# Group_Project_PCB_first_draft.net
KiCad netlist of a schematic drawn in EAGLE
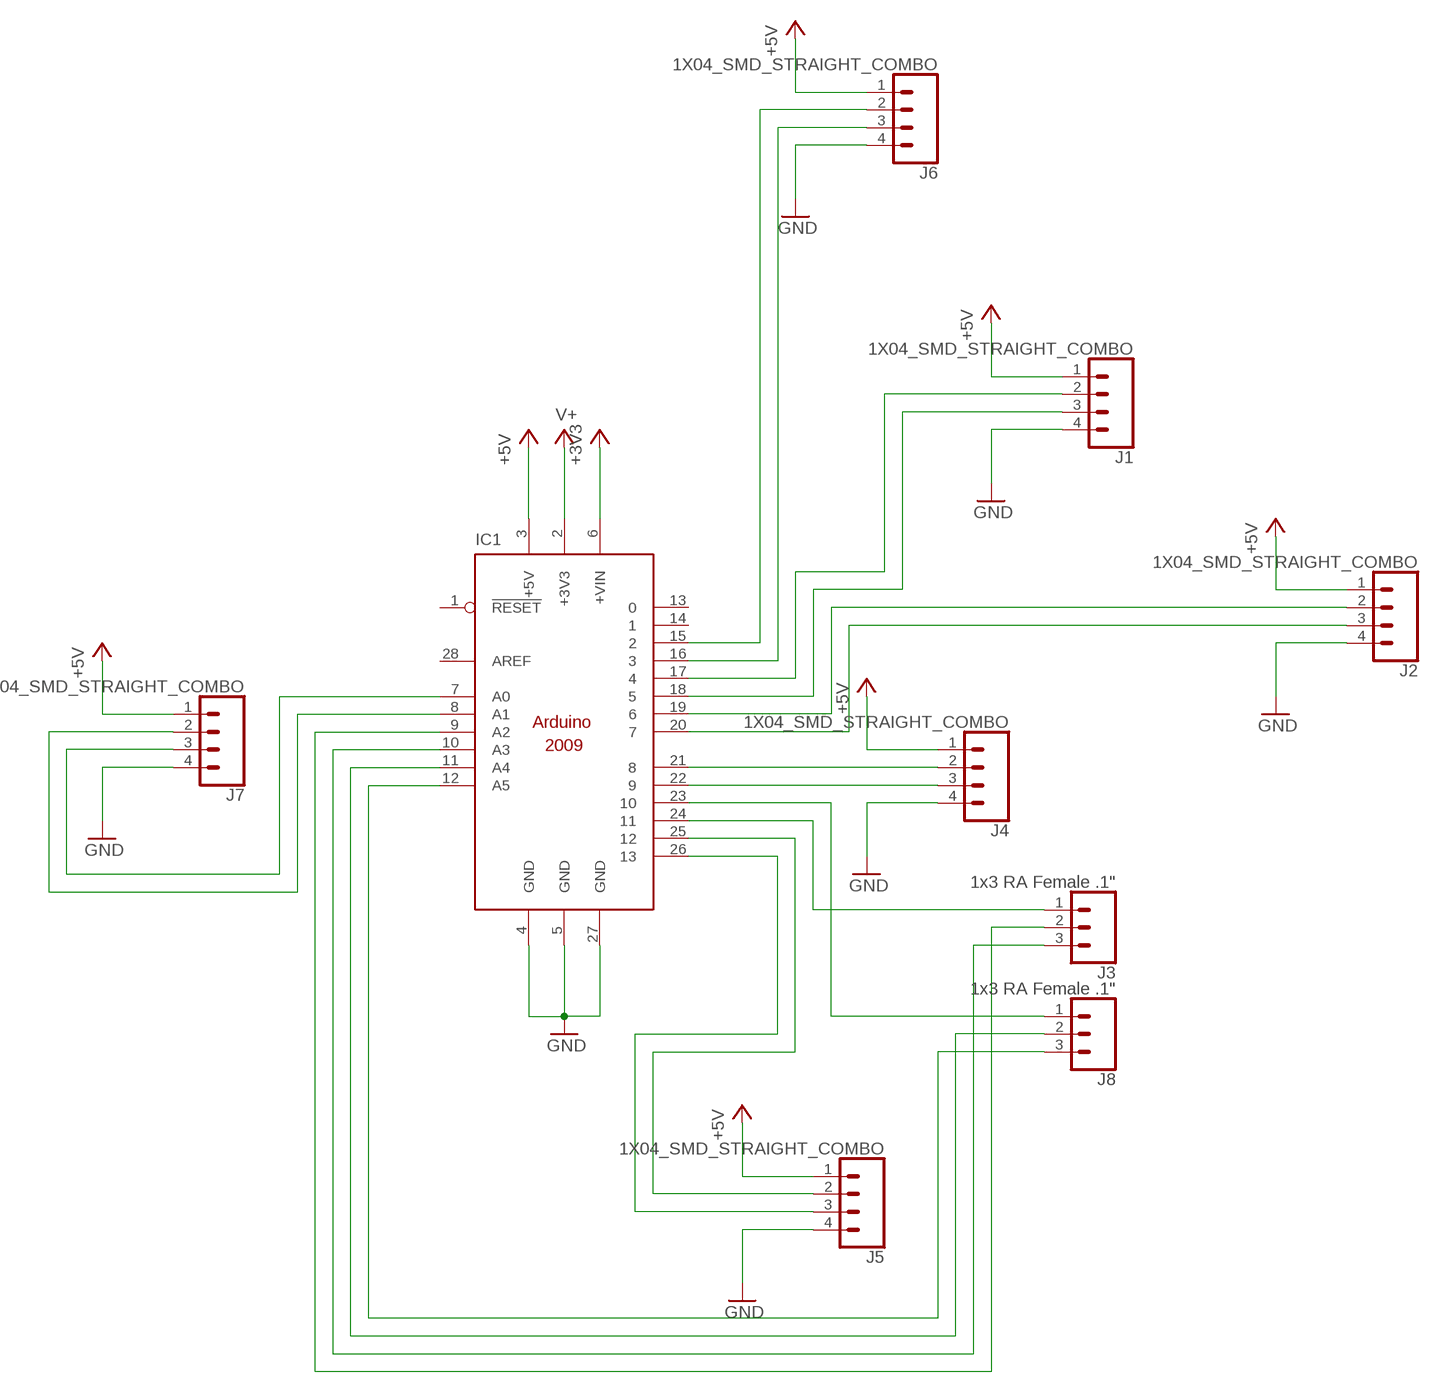
[diagram p0: schematic, sheet 1]

(export (version "E")
  (design (tool "Eeschema 10.0.6"))
  (components
    (comp (ref "IC1")
      (value "ARDUINO2009_10")
      (footprint "eagle-import:ARDUINO2009")
      (libsource (lib "eagle-import") (part "ARDUINO2009_10"))
    )
    (comp (ref "J1")
      (value "1X04_SMD_STRAIGHT_COMBO")
      (footprint "eagle-import:1X04_LONGPADS")
      (libsource (lib "eagle-import") (part "CONN_04LONGPADS"))
    )
    (comp (ref "J2")
      (value "1X04_SMD_STRAIGHT_COMBO")
      (footprint "eagle-import:1X04_LONGPADS")
      (libsource (lib "eagle-import") (part "CONN_04LONGPADS"))
    )
    (comp (ref "J3")
      (value "1x3 RA Female .1\"")
      (footprint "eagle-import:1X03_LONGPADS")
      (libsource (lib "eagle-import") (part "CONN_03LONGPADS"))
    )
    (comp (ref "J4")
      (value "1X04_SMD_STRAIGHT_COMBO")
      (footprint "eagle-import:1X04_LONGPADS")
      (libsource (lib "eagle-import") (part "CONN_04LONGPADS"))
    )
    (comp (ref "J5")
      (value "1X04_SMD_STRAIGHT_COMBO")
      (footprint "eagle-import:1X04_LONGPADS")
      (libsource (lib "eagle-import") (part "CONN_04LONGPADS"))
    )
    (comp (ref "J6")
      (value "1X04_SMD_STRAIGHT_COMBO")
      (footprint "eagle-import:1X04_LONGPADS")
      (libsource (lib "eagle-import") (part "CONN_04LONGPADS"))
    )
    (comp (ref "J7")
      (value "1X04_SMD_STRAIGHT_COMBO")
      (footprint "eagle-import:1X04_LONGPADS")
      (libsource (lib "eagle-import") (part "CONN_04LONGPADS"))
    )
    (comp (ref "J8")
      (value "1x3 RA Female .1\"")
      (footprint "eagle-import:1X03_LONGPADS")
      (libsource (lib "eagle-import") (part "CONN_03LONGPADS"))
    )
  )
  (nets
    (net (code "1") (name "+3V3") (class "Default")
      (node (ref "IC1") (pin "6") (pinfunction "+VIN_6") (pintype "bidirectional"))
    )
    (net (code "2") (name "+5V") (class "Default")
      (node (ref "IC1") (pin "3") (pinfunction "+5V_3") (pintype "power_in"))
      (node (ref "J1") (pin "1") (pinfunction "1_1") (pintype "passive"))
      (node (ref "J2") (pin "1") (pinfunction "1_1") (pintype "passive"))
      (node (ref "J4") (pin "1") (pinfunction "1_1") (pintype "passive"))
      (node (ref "J5") (pin "1") (pinfunction "1_1") (pintype "passive"))
      (node (ref "J6") (pin "1") (pinfunction "1_1") (pintype "passive"))
      (node (ref "J7") (pin "1") (pinfunction "1_1") (pintype "passive"))
    )
    (net (code "3") (name "GND") (class "Default")
      (node (ref "IC1") (pin "27") (pinfunction "GND_27") (pintype "power_in"))
      (node (ref "IC1") (pin "4") (pinfunction "GND_4") (pintype "power_in"))
      (node (ref "IC1") (pin "5") (pinfunction "GND_5") (pintype "power_in"))
      (node (ref "J1") (pin "4") (pinfunction "4_4") (pintype "passive"))
      (node (ref "J2") (pin "4") (pinfunction "4_4") (pintype "passive"))
      (node (ref "J4") (pin "4") (pinfunction "4_4") (pintype "passive"))
      (node (ref "J5") (pin "4") (pinfunction "4_4") (pintype "passive"))
      (node (ref "J6") (pin "4") (pinfunction "4_4") (pintype "passive"))
      (node (ref "J7") (pin "4") (pinfunction "4_4") (pintype "passive"))
    )
    (net (code "4") (name "Net-(IC1-2)") (class "Default")
      (node (ref "IC1") (pin "15") (pinfunction "2_15") (pintype "bidirectional"))
      (node (ref "J6") (pin "2") (pinfunction "2_2") (pintype "passive"))
    )
    (net (code "5") (name "Net-(IC1-3)") (class "Default")
      (node (ref "IC1") (pin "16") (pinfunction "3_16") (pintype "bidirectional"))
      (node (ref "J6") (pin "3") (pinfunction "3_3") (pintype "passive"))
    )
    (net (code "6") (name "Net-(IC1-4)") (class "Default")
      (node (ref "IC1") (pin "17") (pinfunction "4_17") (pintype "bidirectional"))
      (node (ref "J1") (pin "2") (pinfunction "2_2") (pintype "passive"))
    )
    (net (code "7") (name "Net-(IC1-5)") (class "Default")
      (node (ref "IC1") (pin "18") (pinfunction "5_18") (pintype "bidirectional"))
      (node (ref "J1") (pin "3") (pinfunction "3_3") (pintype "passive"))
    )
    (net (code "8") (name "Net-(IC1-6)") (class "Default")
      (node (ref "IC1") (pin "19") (pinfunction "6_19") (pintype "bidirectional"))
      (node (ref "J2") (pin "2") (pinfunction "2_2") (pintype "passive"))
    )
    (net (code "9") (name "Net-(IC1-7)") (class "Default")
      (node (ref "IC1") (pin "20") (pinfunction "7_20") (pintype "bidirectional"))
      (node (ref "J2") (pin "3") (pinfunction "3_3") (pintype "passive"))
    )
    (net (code "10") (name "Net-(IC1-8)") (class "Default")
      (node (ref "IC1") (pin "21") (pinfunction "8_21") (pintype "bidirectional"))
      (node (ref "J4") (pin "2") (pinfunction "2_2") (pintype "passive"))
    )
    (net (code "11") (name "Net-(IC1-9)") (class "Default")
      (node (ref "IC1") (pin "22") (pinfunction "9_22") (pintype "bidirectional"))
      (node (ref "J4") (pin "3") (pinfunction "3_3") (pintype "passive"))
    )
    (net (code "12") (name "Net-(IC1-10)") (class "Default")
      (node (ref "IC1") (pin "23") (pinfunction "10_23") (pintype "bidirectional"))
      (node (ref "J8") (pin "1") (pinfunction "1_1") (pintype "passive"))
    )
    (net (code "13") (name "Net-(IC1-11)") (class "Default")
      (node (ref "IC1") (pin "24") (pinfunction "11_24") (pintype "bidirectional"))
      (node (ref "J3") (pin "1") (pinfunction "1_1") (pintype "passive"))
    )
    (net (code "14") (name "Net-(IC1-12)") (class "Default")
      (node (ref "IC1") (pin "25") (pinfunction "12_25") (pintype "bidirectional"))
      (node (ref "J5") (pin "2") (pinfunction "2_2") (pintype "passive"))
    )
    (net (code "15") (name "Net-(IC1-13)") (class "Default")
      (node (ref "IC1") (pin "26") (pinfunction "13_26") (pintype "bidirectional"))
      (node (ref "J5") (pin "3") (pinfunction "3_3") (pintype "passive"))
    )
    (net (code "16") (name "Net-(IC1-A0)") (class "Default")
      (node (ref "IC1") (pin "7") (pinfunction "A0_7") (pintype "bidirectional"))
      (node (ref "J7") (pin "3") (pinfunction "3_3") (pintype "passive"))
    )
    (net (code "17") (name "Net-(IC1-A1)") (class "Default")
      (node (ref "IC1") (pin "8") (pinfunction "A1_8") (pintype "bidirectional"))
      (node (ref "J7") (pin "2") (pinfunction "2_2") (pintype "passive"))
    )
    (net (code "18") (name "Net-(IC1-A2)") (class "Default")
      (node (ref "IC1") (pin "9") (pinfunction "A2_9") (pintype "bidirectional"))
      (node (ref "J3") (pin "2") (pinfunction "2_2") (pintype "passive"))
    )
    (net (code "19") (name "Net-(IC1-A3)") (class "Default")
      (node (ref "IC1") (pin "10") (pinfunction "A3_10") (pintype "bidirectional"))
      (node (ref "J3") (pin "3") (pinfunction "3_3") (pintype "passive"))
    )
    (net (code "20") (name "Net-(IC1-A4)") (class "Default")
      (node (ref "IC1") (pin "11") (pinfunction "A4_11") (pintype "bidirectional"))
      (node (ref "J8") (pin "2") (pinfunction "2_2") (pintype "passive"))
    )
    (net (code "21") (name "Net-(IC1-A5)") (class "Default")
      (node (ref "IC1") (pin "12") (pinfunction "A5_12") (pintype "bidirectional"))
      (node (ref "J8") (pin "3") (pinfunction "3_3") (pintype "passive"))
    )
    (net (code "22") (name "V+") (class "Default")
      (node (ref "IC1") (pin "2") (pinfunction "+3V3_2") (pintype "power_in"))
    )
    (net (code "23") (name "unconnected-(IC1-0-Pad13)") (class "Default")
      (node (ref "IC1") (pin "13") (pinfunction "0_13") (pintype "bidirectional"))
    )
    (net (code "24") (name "unconnected-(IC1-1-Pad14)") (class "Default")
      (node (ref "IC1") (pin "14") (pinfunction "1_14") (pintype "bidirectional"))
    )
    (net (code "25") (name "unconnected-(IC1-AREF-Pad28)") (class "Default")
      (node (ref "IC1") (pin "28") (pinfunction "AREF_28") (pintype "bidirectional"))
    )
    (net (code "26") (name "unconnected-(IC1-~{RESET}-Pad1)") (class "Default")
      (node (ref "IC1") (pin "1") (pinfunction "~{RESET}_1") (pintype "bidirectional"))
    )
  )
)
